# CVBS2MIPI.net
KiCad netlist of a schematic drawn in Altium Designer
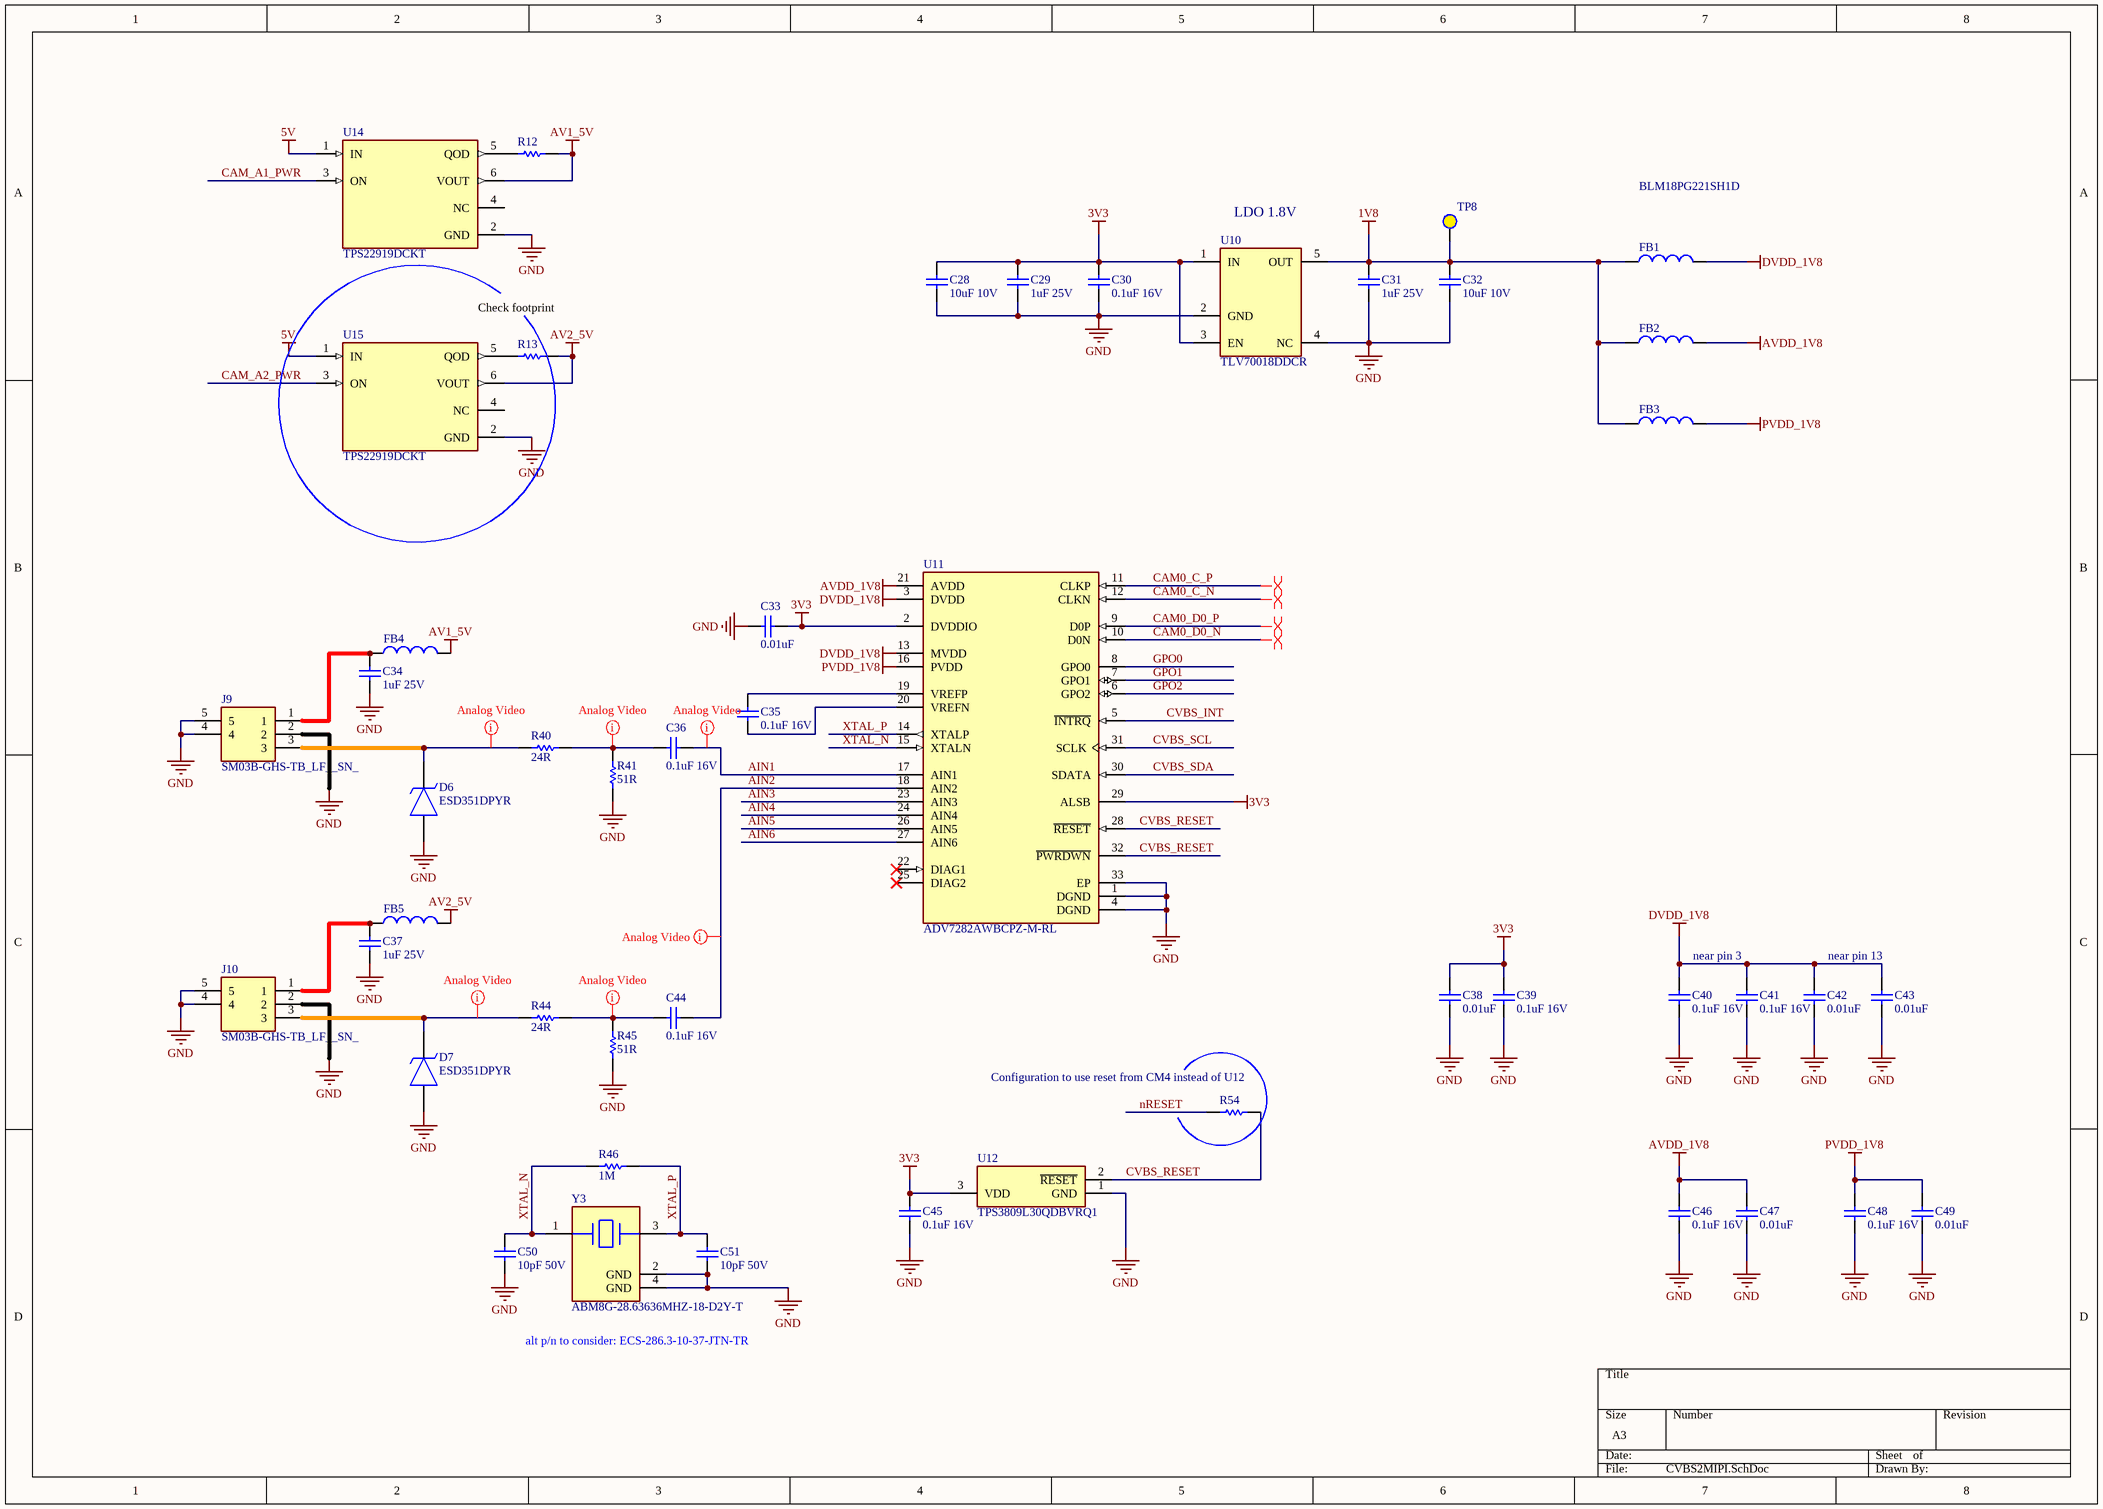
[diagram p0: CVBS2MIPI.SchDoc]

(export (version "E")
  (design (tool "Eeschema 10.0.6"))
  (components
    (comp (ref "C28")
      (value "10uF 10V")
      (footprint "1608[0603]")
      (description "Ceramic Capacitor (Surface Mount) Low ESL")
      (fields
        (field (name "MANUFACTURER") "TDK")
        (field (name "MANUFACTURER PART NUMBER") "C1608X5R1A106M080AC")
      )
      (libsource (lib "MyCustomLibrary") (part "Cap10UF_10V_0603"))
    )
    (comp (ref "C29")
      (value "1uF 25V")
      (footprint "1608[0603]H05")
      (description "Cap Ceramic 1uF 25V X5R 10% 0603")
      (fields
        (field (name "MANUFACTURER") "Samsung")
        (field (name "MANUFACTURER PART NUMBER") "CL10A105KA8NNNC")
      )
      (libsource (lib "MyCustomLibrary") (part "Cap1UF_25V_0603"))
    )
    (comp (ref "C30")
      (value "0.1uF 16V")
      (footprint "0402")
      (description "0402 0.1 uF 16V ±10% Tolerance X7R SMT Multilayer Ceramic Capacitor")
      (fields
        (field (name "MANUFACTURER") "Murata")
        (field (name "MANUFACTURER PART NUMBER") "GCM155R71C104KA55J")
      )
      (libsource (lib "MyCustomLibrary") (part "Cap0.1UF_16V_X7R"))
    )
    (comp (ref "C31")
      (value "1uF 25V")
      (footprint "1608[0603]H05")
      (description "Cap Ceramic 1uF 25V X5R 10% 0603")
      (fields
        (field (name "MANUFACTURER") "Samsung")
        (field (name "MANUFACTURER PART NUMBER") "CL10A105KA8NNNC")
      )
      (libsource (lib "MyCustomLibrary") (part "Cap1UF_25V_0603"))
    )
    (comp (ref "C32")
      (value "10uF 10V")
      (footprint "1608[0603]")
      (description "Ceramic Capacitor (Surface Mount) Low ESL")
      (fields
        (field (name "MANUFACTURER") "TDK")
        (field (name "MANUFACTURER PART NUMBER") "C1608X5R1A106M080AC")
      )
      (libsource (lib "MyCustomLibrary") (part "Cap10UF_10V_0603"))
    )
    (comp (ref "C33")
      (value "0.01uF")
      (footprint "0402")
      (description "Ceramic Capacitor (Surface Mount)")
      (libsource (lib "MyCustomLibrary") (part "Cap0.01UF_25V"))
    )
    (comp (ref "C34")
      (value "1uF 25V")
      (footprint "1608[0603]H05")
      (description "Cap Ceramic 1uF 25V X5R 10% 0603")
      (fields
        (field (name "MANUFACTURER") "Samsung")
        (field (name "MANUFACTURER PART NUMBER") "CL10A105KA8NNNC")
      )
      (libsource (lib "MyCustomLibrary") (part "Cap1UF_25V_0603"))
    )
    (comp (ref "C35")
      (value "0.1uF 16V")
      (footprint "0402")
      (description "0402 0.1 uF 16V ±10% Tolerance X7R SMT Multilayer Ceramic Capacitor")
      (fields
        (field (name "MANUFACTURER") "Murata")
        (field (name "MANUFACTURER PART NUMBER") "GCM155R71C104KA55J")
      )
      (libsource (lib "MyCustomLibrary") (part "Cap0.1UF_16V_X7R"))
    )
    (comp (ref "C36")
      (value "0.1uF 16V")
      (footprint "0402")
      (description "0402 0.1 uF 16V ±10% Tolerance X7R SMT Multilayer Ceramic Capacitor")
      (fields
        (field (name "MANUFACTURER") "Murata")
        (field (name "MANUFACTURER PART NUMBER") "GCM155R71C104KA55J")
      )
      (libsource (lib "MyCustomLibrary") (part "Cap0.1UF_16V_X7R"))
    )
    (comp (ref "C37")
      (value "1uF 25V")
      (footprint "1608[0603]H05")
      (description "Cap Ceramic 1uF 25V X5R 10% 0603")
      (fields
        (field (name "MANUFACTURER") "Samsung")
        (field (name "MANUFACTURER PART NUMBER") "CL10A105KA8NNNC")
      )
      (libsource (lib "MyCustomLibrary") (part "Cap1UF_25V_0603"))
    )
    (comp (ref "C38")
      (value "0.01uF")
      (footprint "0402")
      (description "Ceramic Capacitor (Surface Mount)")
      (libsource (lib "MyCustomLibrary") (part "Cap0.01UF_25V"))
    )
    (comp (ref "C39")
      (value "0.1uF 16V")
      (footprint "0402")
      (description "0402 0.1 uF 16V ±10% Tolerance X7R SMT Multilayer Ceramic Capacitor")
      (fields
        (field (name "MANUFACTURER") "Murata")
        (field (name "MANUFACTURER PART NUMBER") "GCM155R71C104KA55J")
      )
      (libsource (lib "MyCustomLibrary") (part "Cap0.1UF_16V_X7R"))
    )
    (comp (ref "C40")
      (value "0.1uF 16V")
      (footprint "0402")
      (description "0402 0.1 uF 16V ±10% Tolerance X7R SMT Multilayer Ceramic Capacitor")
      (fields
        (field (name "MANUFACTURER") "Murata")
        (field (name "MANUFACTURER PART NUMBER") "GCM155R71C104KA55J")
      )
      (libsource (lib "MyCustomLibrary") (part "Cap0.1UF_16V_X7R"))
    )
    (comp (ref "C41")
      (value "0.1uF 16V")
      (footprint "0402")
      (description "0402 0.1 uF 16V ±10% Tolerance X7R SMT Multilayer Ceramic Capacitor")
      (fields
        (field (name "MANUFACTURER") "Murata")
        (field (name "MANUFACTURER PART NUMBER") "GCM155R71C104KA55J")
      )
      (libsource (lib "MyCustomLibrary") (part "Cap0.1UF_16V_X7R"))
    )
    (comp (ref "C42")
      (value "0.01uF")
      (footprint "0402")
      (description "Ceramic Capacitor (Surface Mount)")
      (libsource (lib "MyCustomLibrary") (part "Cap0.01UF_25V"))
    )
    (comp (ref "C43")
      (value "0.01uF")
      (footprint "0402")
      (description "Ceramic Capacitor (Surface Mount)")
      (libsource (lib "MyCustomLibrary") (part "Cap0.01UF_25V"))
    )
    (comp (ref "C44")
      (value "0.1uF 16V")
      (footprint "0402")
      (description "0402 0.1 uF 16V ±10% Tolerance X7R SMT Multilayer Ceramic Capacitor")
      (fields
        (field (name "MANUFACTURER") "Murata")
        (field (name "MANUFACTURER PART NUMBER") "GCM155R71C104KA55J")
      )
      (libsource (lib "MyCustomLibrary") (part "Cap0.1UF_16V_X7R"))
    )
    (comp (ref "C45")
      (value "0.1uF 16V")
      (footprint "0402")
      (description "0402 0.1 uF 16V ±10% Tolerance X7R SMT Multilayer Ceramic Capacitor")
      (fields
        (field (name "MANUFACTURER") "Murata")
        (field (name "MANUFACTURER PART NUMBER") "GCM155R71C104KA55J")
      )
      (libsource (lib "MyCustomLibrary") (part "Cap0.1UF_16V_X7R"))
    )
    (comp (ref "C46")
      (value "0.1uF 16V")
      (footprint "0402")
      (description "0402 0.1 uF 16V ±10% Tolerance X7R SMT Multilayer Ceramic Capacitor")
      (fields
        (field (name "MANUFACTURER") "Murata")
        (field (name "MANUFACTURER PART NUMBER") "GCM155R71C104KA55J")
      )
      (libsource (lib "MyCustomLibrary") (part "Cap0.1UF_16V_X7R"))
    )
    (comp (ref "C47")
      (value "0.01uF")
      (footprint "0402")
      (description "Ceramic Capacitor (Surface Mount)")
      (libsource (lib "MyCustomLibrary") (part "Cap0.01UF_25V"))
    )
    (comp (ref "C48")
      (value "0.1uF 16V")
      (footprint "0402")
      (description "0402 0.1 uF 16V ±10% Tolerance X7R SMT Multilayer Ceramic Capacitor")
      (fields
        (field (name "MANUFACTURER") "Murata")
        (field (name "MANUFACTURER PART NUMBER") "GCM155R71C104KA55J")
      )
      (libsource (lib "MyCustomLibrary") (part "Cap0.1UF_16V_X7R"))
    )
    (comp (ref "C49")
      (value "0.01uF")
      (footprint "0402")
      (description "Ceramic Capacitor (Surface Mount)")
      (libsource (lib "MyCustomLibrary") (part "Cap0.01UF_25V"))
    )
    (comp (ref "C50")
      (value "10pF 50V")
      (footprint "0402")
      (description "Ceramic Capacitor (Surface Mount)")
      (fields
        (field (name "MANUFACTURER") "Kemet")
        (field (name "MANUFACTURER PART NUMBER") "CBR04C100J5GAC")
      )
      (libsource (lib "MyCustomLibrary") (part "Cap10PF_50V"))
    )
    (comp (ref "C51")
      (value "10pF 50V")
      (footprint "0402")
      (description "Ceramic Capacitor (Surface Mount)")
      (fields
        (field (name "MANUFACTURER") "Kemet")
        (field (name "MANUFACTURER PART NUMBER") "CBR04C100J5GAC")
      )
      (libsource (lib "MyCustomLibrary") (part "Cap10PF_50V"))
    )
    (comp (ref "D6")
      (value "ESD351DPYR")
      (footprint "UCLAMP2501TTCT")
      (fields (field (name "MANUFACTURER") "Texas Instruments"))
      (libsource (lib "MyCustomLibrary") (part "ESD351DPYR"))
    )
    (comp (ref "D7")
      (value "ESD351DPYR")
      (footprint "UCLAMP2501TTCT")
      (fields (field (name "MANUFACTURER") "Texas Instruments"))
      (libsource (lib "MyCustomLibrary") (part "ESD351DPYR"))
    )
    (comp (ref "FB1")
      (value "FerriteBead_120Ohm_2A_0603")
      (footprint "1608[0603]H05")
      (description "FERRITE BEAD 120 OHM 0603 1LN")
      (fields
        (field (name "MANUFACTURER") "TDK")
        (field (name "MANUFACTURER PART NUMBER") "MPZ1608S121ATAH0")
      )
      (libsource (lib "MyCustomLibrary") (part "FerriteBead_120Ohm_2A_0603"))
    )
    (comp (ref "FB2")
      (value "FerriteBead_120Ohm_2A_0603")
      (footprint "1608[0603]H05")
      (description "FERRITE BEAD 120 OHM 0603 1LN")
      (fields
        (field (name "MANUFACTURER") "TDK")
        (field (name "MANUFACTURER PART NUMBER") "MPZ1608S121ATAH0")
      )
      (libsource (lib "MyCustomLibrary") (part "FerriteBead_120Ohm_2A_0603"))
    )
    (comp (ref "FB3")
      (value "FerriteBead_120Ohm_2A_0603")
      (footprint "1608[0603]H05")
      (description "FERRITE BEAD 120 OHM 0603 1LN")
      (fields
        (field (name "MANUFACTURER") "TDK")
        (field (name "MANUFACTURER PART NUMBER") "MPZ1608S121ATAH0")
      )
      (libsource (lib "MyCustomLibrary") (part "FerriteBead_120Ohm_2A_0603"))
    )
    (comp (ref "FB4")
      (value "FerriteBead_120Ohm_2A_0603")
      (footprint "1608[0603]H05")
      (description "FERRITE BEAD 120 OHM 0603 1LN")
      (fields
        (field (name "MANUFACTURER") "TDK")
        (field (name "MANUFACTURER PART NUMBER") "MPZ1608S121ATAH0")
      )
      (libsource (lib "MyCustomLibrary") (part "FerriteBead_120Ohm_2A_0603"))
    )
    (comp (ref "FB5")
      (value "FerriteBead_120Ohm_2A_0603")
      (footprint "1608[0603]H05")
      (description "FERRITE BEAD 120 OHM 0603 1LN")
      (fields
        (field (name "MANUFACTURER") "TDK")
        (field (name "MANUFACTURER PART NUMBER") "MPZ1608S121ATAH0")
      )
      (libsource (lib "MyCustomLibrary") (part "FerriteBead_120Ohm_2A_0603"))
    )
    (comp (ref "J9")
      (value "SM03B-GHS-TB_LF__SN_")
      (footprint "SM03BGHSTBLFSN")
      (description "Connector")
      (fields
        (field (name "MANUFACTURER_PART_NUMBER") "SM03B-GHS-TB(LF)(SN)")
        (field (name "MANUFACTURER") "JST")
      )
      (libsource (lib "MyConnectors") (part "SM03B-GHS-TB_LF__SN_"))
    )
    (comp (ref "J10")
      (value "SM03B-GHS-TB_LF__SN_")
      (footprint "SM03BGHSTBLFSN")
      (description "Connector")
      (fields
        (field (name "MANUFACTURER_PART_NUMBER") "SM03B-GHS-TB(LF)(SN)")
        (field (name "MANUFACTURER") "JST")
      )
      (libsource (lib "MyConnectors") (part "SM03B-GHS-TB_LF__SN_"))
    )
    (comp (ref "R12")
      (value "0R")
      (footprint "0402")
      (description "Zero ohm Jumper 0402")
      (fields
        (field (name "MANUFACTURER") "Yageo")
        (field (name "MANUFACTURER PART NUMBER") "RC0402JR-070RL")
      )
      (libsource (lib "MyCustomLibrary") (part "Res_0R_0402"))
    )
    (comp (ref "R13")
      (value "0R")
      (footprint "0402")
      (description "Zero ohm Jumper 0402")
      (fields
        (field (name "MANUFACTURER") "Yageo")
        (field (name "MANUFACTURER PART NUMBER") "RC0402JR-070RL")
      )
      (libsource (lib "MyCustomLibrary") (part "Res_0R_0402"))
    )
    (comp (ref "R40")
      (value "24R")
      (footprint "0402")
      (description "SMD Chip Resistor, 24 Ohm, ± 1%, 63 mW, 0402 [1005 Metric], Thick Film, General Purpose")
      (fields
        (field (name "MANUFACTURER") "Yageo")
        (field (name "MANUFACTURER PART NUMBER") "RC0402FR-0724RL")
      )
      (libsource (lib "MyCustomLibrary") (part "Res_24R_0402"))
    )
    (comp (ref "R41")
      (value "51R")
      (footprint "0402")
      (description "SMD Chip Resistor, 51 Ohm, ± 1%, 63 mW, 0402 [1005 Metric], Thick Film, General Purpose")
      (fields
        (field (name "MANUFACTURER") "Yageo")
        (field (name "MANUFACTURER PART NUMBER") "AC0402FR-0751RL")
      )
      (libsource (lib "MyCustomLibrary") (part "Res_51R_0402"))
    )
    (comp (ref "R44")
      (value "24R")
      (footprint "0402")
      (description "SMD Chip Resistor, 24 Ohm, ± 1%, 63 mW, 0402 [1005 Metric], Thick Film, General Purpose")
      (fields
        (field (name "MANUFACTURER") "Yageo")
        (field (name "MANUFACTURER PART NUMBER") "RC0402FR-0724RL")
      )
      (libsource (lib "MyCustomLibrary") (part "Res_24R_0402"))
    )
    (comp (ref "R45")
      (value "51R")
      (footprint "0402")
      (description "SMD Chip Resistor, 51 Ohm, ± 1%, 63 mW, 0402 [1005 Metric], Thick Film, General Purpose")
      (fields
        (field (name "MANUFACTURER") "Yageo")
        (field (name "MANUFACTURER PART NUMBER") "AC0402FR-0751RL")
      )
      (libsource (lib "MyCustomLibrary") (part "Res_51R_0402"))
    )
    (comp (ref "R46")
      (value "1M")
      (footprint "0402")
      (description "Resistor")
      (fields
        (field (name "MANUFACTURER") "Stackpole Electronics Inc")
        (field (name "MANUFACTURER PART NUMBER") "RMCF0402FT1M00")
      )
      (libsource (lib "MyCustomLibrary") (part "Res_1M_0402"))
    )
    (comp (ref "R54")
      (value "0R")
      (footprint "0402")
      (description "Zero ohm Jumper 0402")
      (fields
        (field (name "MANUFACTURER") "Yageo")
        (field (name "MANUFACTURER PART NUMBER") "RC0402JR-070RL")
      )
      (libsource (lib "MyCustomLibrary") (part "Res_0R_0402"))
    )
    (comp (ref "TP8")
      (value "TESTPOINT")
      (footprint "TESTPOINT_0.9")
      (libsource (lib "MyCustomLibrary") (part "TESTPOINT"))
    )
    (comp (ref "U10")
      (value "TLV70018DDCR")
      (footprint "SOT95P280X110-5N")
      (description "IC REG LINEAR 1.8V 200MA SOT23-5")
      (fields
        (field (name "MOUSER PART NUMBER") "595-TLV70018DDCR")
        (field (name "MANUFACTURER") "Texas Instruments")
      )
      (libsource (lib "MyCustomLibrary") (part "TLV70018DDCR"))
    )
    (comp (ref "U11")
      (value "ADV7282AWBCPZ-M-RL")
      (footprint "FP-CP-32-12-IPC_C")
      (description "Video Decoder 1ADC 10bit Automotive 32-Pin LFCSP EP T/R")
      (fields (field (name "MANUFACTURER") "Analog Devices"))
      (libsource (lib "MyCustomLibrary") (part "ADV7282A"))
    )
    (comp (ref "U12")
      (value "TPS3809L30QDBVRQ1")
      (footprint "VCP:SOT95P280X145-3N")
      (fields
        (field (name "MOUSER PART NUMBER") "595-TPS3809L30QDBVRQ")
        (field (name "MANUFACTURER") "Texas Instruments")
      )
      (libsource (lib "VCP") (part "TPS3809L30QDBVRQ1"))
    )
    (comp (ref "U14")
      (value "TPS22919DCKT")
      (footprint "FP-DCK0006A-MFG")
      (description "IC PWR SWITCH N-CHAN 1:1 SC70-6")
      (libsource (lib "Altium Content Vault") (part "e7d5fd3352266f557688e217cb769b6"))
    )
    (comp (ref "U15")
      (value "TPS22919DCKT")
      (footprint "FP-DCK0006A-MFG")
      (description "IC PWR SWITCH N-CHAN 1:1 SC70-6")
      (libsource (lib "Altium Content Vault") (part "e7d5fd3352266f557688e217cb769b6"))
    )
    (comp (ref "Y3")
      (value "ABM8G-28.63636MHZ-18-D2Y-T")
      (footprint "FP-ABM8G-MFG")
      (description "Crystal 28.63636MHz ±20ppm (Tol) ±30ppm (Stability) 18pF FUND 50Ω 4-Pin SMD T/R")
      (fields (field (name "TOLERANCE") "20ppm"))
      (libsource (lib "MyCustomLibrary") (part "Crystal_28.63636MHz"))
    )
  )
  (nets
    (net (code "1") (name "/AIN1") (class "Default")
      (node (ref "C36") (pin "1") (pinfunction "1_1") (pintype "passive"))
      (node (ref "U11") (pin "17") (pinfunction "AIN1_17") (pintype "passive"))
    )
    (net (code "2") (name "/AIN2") (class "Default")
      (node (ref "C44") (pin "1") (pinfunction "1_1") (pintype "passive"))
      (node (ref "U11") (pin "18") (pinfunction "AIN2_18") (pintype "passive"))
    )
    (net (code "3") (name "/AIN3") (class "Default")
      (node (ref "U11") (pin "23") (pinfunction "AIN3_23") (pintype "power_in"))
    )
    (net (code "4") (name "/AIN4") (class "Default")
      (node (ref "U11") (pin "24") (pinfunction "AIN4_24") (pintype "power_in"))
    )
    (net (code "5") (name "/AIN5") (class "Default")
      (node (ref "U11") (pin "26") (pinfunction "AIN5_26") (pintype "power_in"))
    )
    (net (code "6") (name "/AIN6") (class "Default")
      (node (ref "U11") (pin "27") (pinfunction "AIN6_27") (pintype "power_in"))
    )
    (net (code "7") (name "/CAM0_C_N") (class "Default")
      (node (ref "U11") (pin "12") (pinfunction "CLKN_12") (pintype "input"))
    )
    (net (code "8") (name "/CAM0_C_P") (class "Default")
      (node (ref "U11") (pin "11") (pinfunction "CLKP_11") (pintype "input"))
    )
    (net (code "9") (name "/CAM0_D0_N") (class "Default")
      (node (ref "U11") (pin "10") (pinfunction "D0N_10") (pintype "input"))
    )
    (net (code "10") (name "/CAM0_D0_P") (class "Default")
      (node (ref "U11") (pin "9") (pinfunction "D0P_9") (pintype "input"))
    )
    (net (code "11") (name "/CAM_A1_PWR") (class "Default")
      (node (ref "U14") (pin "3") (pinfunction "ON_3") (pintype "input"))
    )
    (net (code "12") (name "/CAM_A2_PWR") (class "Default")
      (node (ref "U15") (pin "3") (pinfunction "ON_3") (pintype "input"))
    )
    (net (code "13") (name "/CVBS_INT") (class "Default")
      (node (ref "U11") (pin "5") (pinfunction "~{INTRQ}_5") (pintype "input"))
    )
    (net (code "14") (name "/CVBS_RESET") (class "Default")
      (node (ref "R54") (pin "2") (pinfunction "2_2") (pintype "passive"))
      (node (ref "U11") (pin "28") (pinfunction "~{RESET}_28") (pintype "input"))
      (node (ref "U11") (pin "32") (pinfunction "~{PWRDWN}_32") (pintype "open_collector"))
      (node (ref "U12") (pin "2") (pinfunction "~{RESET}_2") (pintype "passive"))
    )
    (net (code "15") (name "/CVBS_SCL") (class "Default")
      (node (ref "U11") (pin "31") (pinfunction "SCLK_31") (pintype "input"))
    )
    (net (code "16") (name "/CVBS_SDA") (class "Default")
      (node (ref "U11") (pin "30") (pinfunction "SDATA_30") (pintype "input"))
    )
    (net (code "17") (name "/GPO0") (class "Default")
      (node (ref "U11") (pin "8") (pinfunction "GPO0_8") (pintype "open_collector"))
    )
    (net (code "18") (name "/GPO1") (class "Default")
      (node (ref "U11") (pin "7") (pinfunction "GPO1_7") (pintype "bidirectional"))
    )
    (net (code "19") (name "/GPO2") (class "Default")
      (node (ref "U11") (pin "6") (pinfunction "GPO2_6") (pintype "bidirectional"))
    )
    (net (code "20") (name "/XTAL_N") (class "Default")
      (node (ref "C50") (pin "2") (pinfunction "2_2") (pintype "passive"))
      (node (ref "R46") (pin "1") (pinfunction "1_1") (pintype "passive"))
      (node (ref "U11") (pin "15") (pinfunction "XTALN_15") (pintype "input"))
      (node (ref "Y3") (pin "1") (pinfunction "1_1") (pintype "passive"))
    )
    (net (code "21") (name "/XTAL_P") (class "Default")
      (node (ref "C51") (pin "2") (pinfunction "2_2") (pintype "passive"))
      (node (ref "R46") (pin "2") (pinfunction "2_2") (pintype "passive"))
      (node (ref "U11") (pin "14") (pinfunction "XTALP_14") (pintype "output"))
      (node (ref "Y3") (pin "3") (pinfunction "3_3") (pintype "passive"))
    )
    (net (code "22") (name "/nRESET") (class "Default")
      (node (ref "R54") (pin "1") (pinfunction "1_1") (pintype "passive"))
    )
    (net (code "23") (name "1V8") (class "Default")
      (node (ref "C31") (pin "2") (pinfunction "2_2") (pintype "passive"))
      (node (ref "C32") (pin "2") (pinfunction "2_2") (pintype "passive"))
      (node (ref "FB1") (pin "1") (pinfunction "1_1") (pintype "passive"))
      (node (ref "FB2") (pin "1") (pinfunction "1_1") (pintype "passive"))
      (node (ref "FB3") (pin "1") (pinfunction "1_1") (pintype "passive"))
      (node (ref "TP8") (pin "1") (pinfunction "1_1") (pintype "passive"))
      (node (ref "U10") (pin "5") (pinfunction "OUT_5") (pintype "passive"))
    )
    (net (code "24") (name "3V3") (class "Default")
      (node (ref "C28") (pin "2") (pinfunction "2_2") (pintype "passive"))
      (node (ref "C29") (pin "2") (pinfunction "2_2") (pintype "passive"))
      (node (ref "C30") (pin "1") (pinfunction "1_1") (pintype "passive"))
      (node (ref "C33") (pin "1") (pinfunction "1_1") (pintype "passive"))
      (node (ref "C38") (pin "2") (pinfunction "2_2") (pintype "passive"))
      (node (ref "C39") (pin "1") (pinfunction "1_1") (pintype "passive"))
      (node (ref "C45") (pin "1") (pinfunction "1_1") (pintype "passive"))
      (node (ref "U10") (pin "1") (pinfunction "IN_1") (pintype "passive"))
      (node (ref "U10") (pin "3") (pinfunction "EN_3") (pintype "passive"))
      (node (ref "U11") (pin "2") (pinfunction "DVDDIO_2") (pintype "power_in"))
      (node (ref "U11") (pin "29") (pinfunction "ALSB_29") (pintype "passive"))
      (node (ref "U12") (pin "3") (pinfunction "VDD_3") (pintype "power_in"))
    )
    (net (code "25") (name "5V") (class "Default")
      (node (ref "U14") (pin "1") (pinfunction "IN_1") (pintype "input"))
      (node (ref "U15") (pin "1") (pinfunction "IN_1") (pintype "input"))
    )
    (net (code "26") (name "AV1_5V") (class "Default")
      (node (ref "FB4") (pin "2") (pinfunction "2_2") (pintype "passive"))
      (node (ref "R12") (pin "2") (pinfunction "2_2") (pintype "passive"))
      (node (ref "U14") (pin "6") (pinfunction "VOUT_6") (pintype "output"))
    )
    (net (code "27") (name "AV2_5V") (class "Default")
      (node (ref "FB5") (pin "2") (pinfunction "2_2") (pintype "passive"))
      (node (ref "R13") (pin "2") (pinfunction "2_2") (pintype "passive"))
      (node (ref "U15") (pin "6") (pinfunction "VOUT_6") (pintype "output"))
    )
    (net (code "28") (name "AVDD_1V8") (class "Default")
      (node (ref "C46") (pin "1") (pinfunction "1_1") (pintype "passive"))
      (node (ref "C47") (pin "2") (pinfunction "2_2") (pintype "passive"))
      (node (ref "FB2") (pin "2") (pinfunction "2_2") (pintype "passive"))
      (node (ref "U11") (pin "21") (pinfunction "AVDD_21") (pintype "power_in"))
    )
    (net (code "29") (name "DVDD_1V8") (class "Default")
      (node (ref "C40") (pin "1") (pinfunction "1_1") (pintype "passive"))
      (node (ref "C41") (pin "1") (pinfunction "1_1") (pintype "passive"))
      (node (ref "C42") (pin "2") (pinfunction "2_2") (pintype "passive"))
      (node (ref "C43") (pin "2") (pinfunction "2_2") (pintype "passive"))
      (node (ref "FB1") (pin "2") (pinfunction "2_2") (pintype "passive"))
      (node (ref "U11") (pin "13") (pinfunction "MVDD_13") (pintype "power_in"))
      (node (ref "U11") (pin "3") (pinfunction "DVDD_3") (pintype "power_in"))
    )
    (net (code "30") (name "GND") (class "Default")
      (node (ref "C28") (pin "1") (pinfunction "1_1") (pintype "passive"))
      (node (ref "C29") (pin "1") (pinfunction "1_1") (pintype "passive"))
      (node (ref "C30") (pin "2") (pinfunction "2_2") (pintype "passive"))
      (node (ref "C31") (pin "1") (pinfunction "1_1") (pintype "passive"))
      (node (ref "C32") (pin "1") (pinfunction "1_1") (pintype "passive"))
      (node (ref "C33") (pin "2") (pinfunction "2_2") (pintype "passive"))
      (node (ref "C34") (pin "1") (pinfunction "1_1") (pintype "passive"))
      (node (ref "C37") (pin "1") (pinfunction "1_1") (pintype "passive"))
      (node (ref "C38") (pin "1") (pinfunction "1_1") (pintype "passive"))
      (node (ref "C39") (pin "2") (pinfunction "2_2") (pintype "passive"))
      (node (ref "C40") (pin "2") (pinfunction "2_2") (pintype "passive"))
      (node (ref "C41") (pin "2") (pinfunction "2_2") (pintype "passive"))
      (node (ref "C42") (pin "1") (pinfunction "1_1") (pintype "passive"))
      (node (ref "C43") (pin "1") (pinfunction "1_1") (pintype "passive"))
      (node (ref "C45") (pin "2") (pinfunction "2_2") (pintype "passive"))
      (node (ref "C46") (pin "2") (pinfunction "2_2") (pintype "passive"))
      (node (ref "C47") (pin "1") (pinfunction "1_1") (pintype "passive"))
      (node (ref "C48") (pin "2") (pinfunction "2_2") (pintype "passive"))
      (node (ref "C49") (pin "1") (pinfunction "1_1") (pintype "passive"))
      (node (ref "C50") (pin "1") (pinfunction "1_1") (pintype "passive"))
      (node (ref "C51") (pin "1") (pinfunction "1_1") (pintype "passive"))
      (node (ref "D6") (pin "1") (pinfunction "A_1") (pintype "passive"))
      (node (ref "D7") (pin "1") (pinfunction "A_1") (pintype "passive"))
      (node (ref "J10") (pin "2") (pinfunction "2_2") (pintype "passive"))
      (node (ref "J10") (pin "4") (pinfunction "4_4") (pintype "passive"))
      (node (ref "J10") (pin "5") (pinfunction "5_5") (pintype "passive"))
      (node (ref "J9") (pin "2") (pinfunction "2_2") (pintype "passive"))
      (node (ref "J9") (pin "4") (pinfunction "4_4") (pintype "passive"))
      (node (ref "J9") (pin "5") (pinfunction "5_5") (pintype "passive"))
      (node (ref "R41") (pin "1") (pinfunction "1_1") (pintype "passive"))
      (node (ref "R45") (pin "1") (pinfunction "1_1") (pintype "passive"))
      (node (ref "U10") (pin "2") (pinfunction "GND_2") (pintype "passive"))
      (node (ref "U10") (pin "4") (pinfunction "NC_4") (pintype "passive"))
      (node (ref "U11") (pin "1") (pinfunction "DGND_1") (pintype "power_in"))
      (node (ref "U11") (pin "33") (pinfunction "EP_33") (pintype "power_in"))
      (node (ref "U11") (pin "4") (pinfunction "DGND_4") (pintype "power_in"))
      (node (ref "U12") (pin "1") (pinfunction "GND_1") (pintype "power_in"))
      (node (ref "U14") (pin "2") (pinfunction "GND_2") (pintype "power_in"))
      (node (ref "U15") (pin "2") (pinfunction "GND_2") (pintype "power_in"))
      (node (ref "Y3") (pin "2") (pinfunction "GND_2") (pintype "power_in"))
      (node (ref "Y3") (pin "4") (pinfunction "GND_4") (pintype "power_in"))
    )
    (net (code "31") (name "Net-(C34-Pad2)") (class "Default")
      (node (ref "C34") (pin "2") (pinfunction "2_2") (pintype "passive"))
      (node (ref "FB4") (pin "1") (pinfunction "1_1") (pintype "passive"))
      (node (ref "J9") (pin "1") (pinfunction "1_1") (pintype "passive"))
    )
    (net (code "32") (name "Net-(C36-Pad2)") (class "Default")
      (node (ref "C36") (pin "2") (pinfunction "2_2") (pintype "passive"))
      (node (ref "R40") (pin "2") (pinfunction "2_2") (pintype "passive"))
      (node (ref "R41") (pin "2") (pinfunction "2_2") (pintype "passive"))
    )
    (net (code "33") (name "Net-(C37-Pad2)") (class "Default")
      (node (ref "C37") (pin "2") (pinfunction "2_2") (pintype "passive"))
      (node (ref "FB5") (pin "1") (pinfunction "1_1") (pintype "passive"))
      (node (ref "J10") (pin "1") (pinfunction "1_1") (pintype "passive"))
    )
    (net (code "34") (name "Net-(C44-Pad2)") (class "Default")
      (node (ref "C44") (pin "2") (pinfunction "2_2") (pintype "passive"))
      (node (ref "R44") (pin "2") (pinfunction "2_2") (pintype "passive"))
      (node (ref "R45") (pin "2") (pinfunction "2_2") (pintype "passive"))
    )
    (net (code "35") (name "Net-(D6-K)") (class "Default")
      (node (ref "D6") (pin "2") (pinfunction "K_2") (pintype "passive"))
      (node (ref "J9") (pin "3") (pinfunction "3_3") (pintype "passive"))
      (node (ref "R40") (pin "1") (pinfunction "1_1") (pintype "passive"))
    )
    (net (code "36") (name "Net-(D7-K)") (class "Default")
      (node (ref "D7") (pin "2") (pinfunction "K_2") (pintype "passive"))
      (node (ref "J10") (pin "3") (pinfunction "3_3") (pintype "passive"))
      (node (ref "R44") (pin "1") (pinfunction "1_1") (pintype "passive"))
    )
    (net (code "37") (name "Net-(U11-VREFN)") (class "Default")
      (node (ref "C35") (pin "2") (pinfunction "2_2") (pintype "passive"))
      (node (ref "U11") (pin "20") (pinfunction "VREFN_20") (pintype "passive"))
    )
    (net (code "38") (name "Net-(U11-VREFP)") (class "Default")
      (node (ref "C35") (pin "1") (pinfunction "1_1") (pintype "passive"))
      (node (ref "U11") (pin "19") (pinfunction "VREFP_19") (pintype "passive"))
    )
    (net (code "39") (name "Net-(U14-QOD)") (class "Default")
      (node (ref "R12") (pin "1") (pinfunction "1_1") (pintype "passive"))
      (node (ref "U14") (pin "5") (pinfunction "QOD_5") (pintype "output"))
    )
    (net (code "40") (name "Net-(U15-QOD)") (class "Default")
      (node (ref "R13") (pin "1") (pinfunction "1_1") (pintype "passive"))
      (node (ref "U15") (pin "5") (pinfunction "QOD_5") (pintype "output"))
    )
    (net (code "41") (name "PVDD_1V8") (class "Default")
      (node (ref "C48") (pin "1") (pinfunction "1_1") (pintype "passive"))
      (node (ref "C49") (pin "2") (pinfunction "2_2") (pintype "passive"))
      (node (ref "FB3") (pin "2") (pinfunction "2_2") (pintype "passive"))
      (node (ref "U11") (pin "16") (pinfunction "PVDD_16") (pintype "power_in"))
    )
    (net (code "42") (name "unconnected-(U11-DIAG1-Pad22)") (class "Default")
      (node (ref "U11") (pin "22") (pinfunction "DIAG1_22") (pintype "input+no_connect"))
    )
    (net (code "43") (name "unconnected-(U11-DIAG2-Pad25)") (class "Default")
      (node (ref "U11") (pin "25") (pinfunction "DIAG2_25") (pintype "passive+no_connect"))
    )
    (net (code "44") (name "unconnected-(U14-NC-Pad4)") (class "Default")
      (node (ref "U14") (pin "4") (pinfunction "NC_4") (pintype "passive"))
    )
    (net (code "45") (name "unconnected-(U15-NC-Pad4)") (class "Default")
      (node (ref "U15") (pin "4") (pinfunction "NC_4") (pintype "passive"))
    )
  )
)
